# AS3364_quad_VCA_0402_DIL-non_inv_v1_0.net
KiCad netlist of a schematic drawn in EAGLE
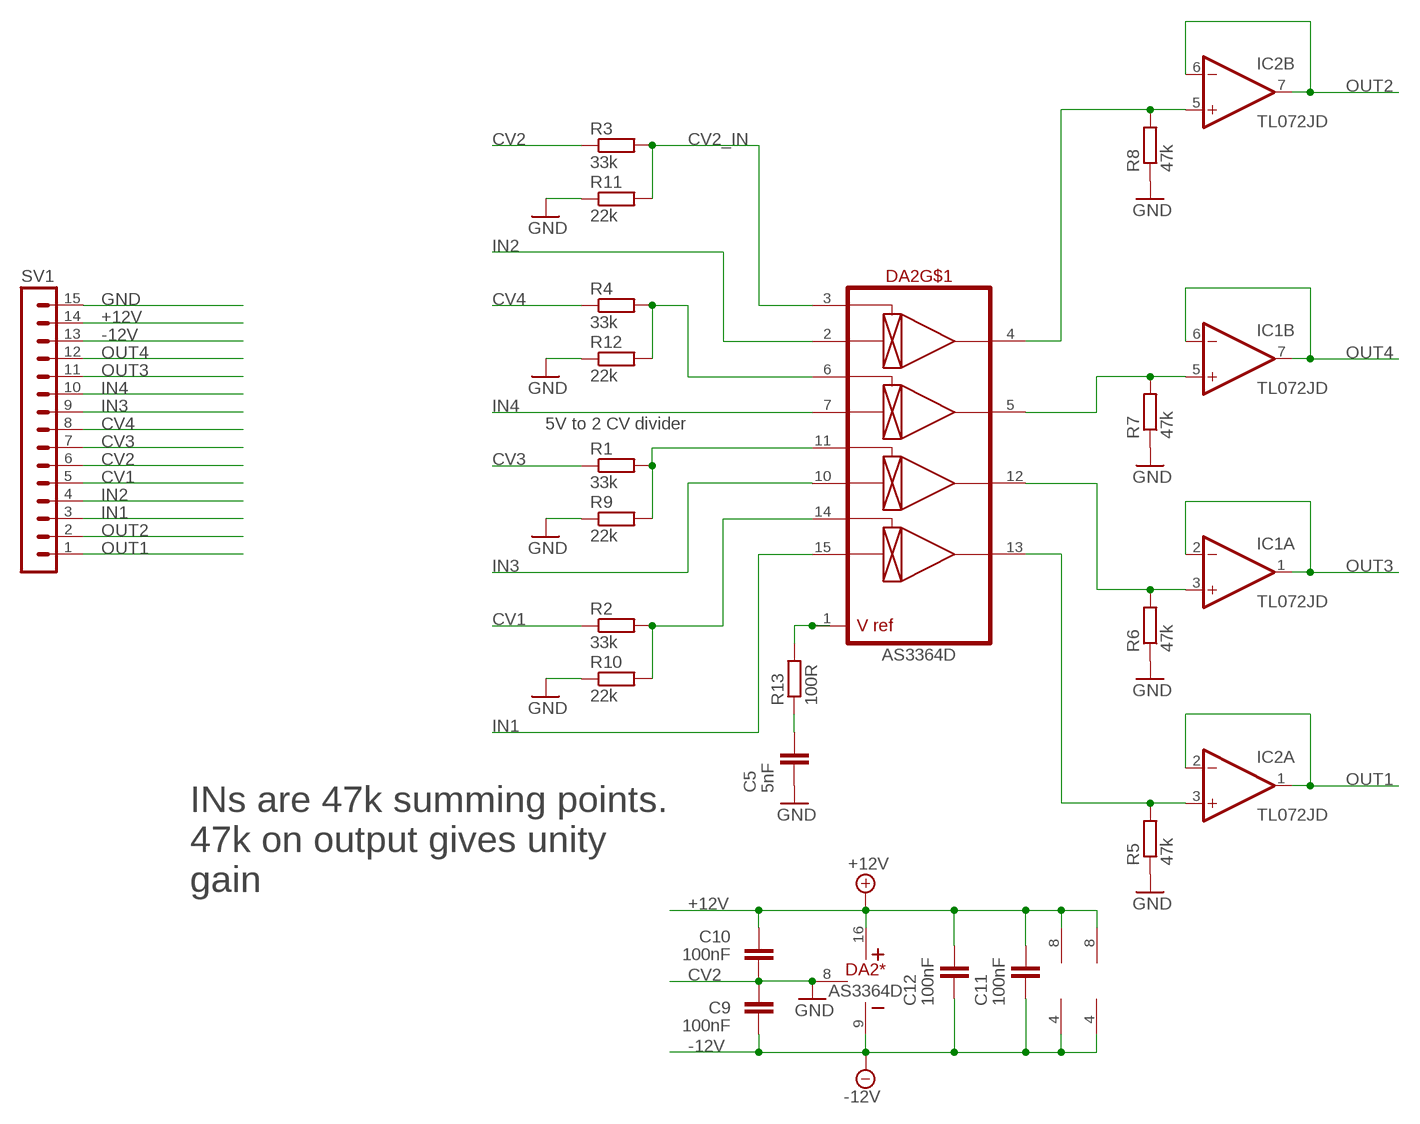
[diagram p0: schematic, sheet 1]

(export (version "E")
  (design (tool "Eeschema 10.0.6"))
  (components
    (comp (ref "C5")
      (value "5nF")
      (footprint "eagle-import:C0402")
      (libsource (lib "eagle-import") (part "C-EUC0402"))
    )
    (comp (ref "C9")
      (value "100nF")
      (footprint "eagle-import:C0402")
      (libsource (lib "eagle-import") (part "C-EUC0402"))
    )
    (comp (ref "C10")
      (value "100nF")
      (footprint "eagle-import:C0402")
      (libsource (lib "eagle-import") (part "C-EUC0402"))
    )
    (comp (ref "C11")
      (value "100nF")
      (footprint "eagle-import:C0402")
      (libsource (lib "eagle-import") (part "C-EUC0402"))
    )
    (comp (ref "C12")
      (value "100nF")
      (footprint "eagle-import:C0402")
      (libsource (lib "eagle-import") (part "C-EUC0402"))
    )
    (comp (ref "DA2")
      (value "AS3364D")
      (footprint "eagle-import:DIL16J")
      (libsource (lib "eagle-import") (part "AS3364D"))
    )
    (comp (ref "IC1")
      (value "TL072JD")
      (footprint "eagle-import:SO08J")
      (libsource (lib "eagle-import") (part "TL072JD"))
    )
    (comp (ref "IC2")
      (value "TL072JD")
      (footprint "eagle-import:SO08J")
      (libsource (lib "eagle-import") (part "TL072JD"))
    )
    (comp (ref "R1")
      (value "33k")
      (footprint "eagle-import:R0402")
      (libsource (lib "eagle-import") (part "R-EU_R0402"))
    )
    (comp (ref "R2")
      (value "33k")
      (footprint "eagle-import:R0402")
      (libsource (lib "eagle-import") (part "R-EU_R0402"))
    )
    (comp (ref "R3")
      (value "33k")
      (footprint "eagle-import:R0402")
      (libsource (lib "eagle-import") (part "R-EU_R0402"))
    )
    (comp (ref "R4")
      (value "33k")
      (footprint "eagle-import:R0402")
      (libsource (lib "eagle-import") (part "R-EU_R0402"))
    )
    (comp (ref "R5")
      (value "47k")
      (footprint "eagle-import:R0402")
      (libsource (lib "eagle-import") (part "R-EU_R0402"))
    )
    (comp (ref "R6")
      (value "47k")
      (footprint "eagle-import:R0402")
      (libsource (lib "eagle-import") (part "R-EU_R0402"))
    )
    (comp (ref "R7")
      (value "47k")
      (footprint "eagle-import:R0402")
      (libsource (lib "eagle-import") (part "R-EU_R0402"))
    )
    (comp (ref "R8")
      (value "47k")
      (footprint "eagle-import:R0402")
      (libsource (lib "eagle-import") (part "R-EU_R0402"))
    )
    (comp (ref "R9")
      (value "22k")
      (footprint "eagle-import:R0402")
      (libsource (lib "eagle-import") (part "R-EU_R0402"))
    )
    (comp (ref "R10")
      (value "22k")
      (footprint "eagle-import:R0402")
      (libsource (lib "eagle-import") (part "R-EU_R0402"))
    )
    (comp (ref "R11")
      (value "22k")
      (footprint "eagle-import:R0402")
      (libsource (lib "eagle-import") (part "R-EU_R0402"))
    )
    (comp (ref "R12")
      (value "22k")
      (footprint "eagle-import:R0402")
      (libsource (lib "eagle-import") (part "R-EU_R0402"))
    )
    (comp (ref "R13")
      (value "100R")
      (footprint "eagle-import:R0402")
      (libsource (lib "eagle-import") (part "R-EU_R0402"))
    )
    (comp (ref "SV1")
      (value "MA15-1JP")
      (footprint "eagle-import:SIP-PIN15-1J")
      (libsource (lib "eagle-import") (part "MA15-1JP"))
    )
  )
  (nets
    (net (code "1") (name "+12V") (class "Default")
      (node (ref "C10") (pin "2") (pinfunction "2_2") (pintype "passive"))
      (node (ref "C11") (pin "2") (pinfunction "2_2") (pintype "passive"))
      (node (ref "C12") (pin "2") (pinfunction "2_2") (pintype "passive"))
      (node (ref "DA2") (pin "16") (pinfunction "V+_16") (pintype "power_in"))
      (node (ref "IC1") (pin "8") (pinfunction "V+_8") (pintype "power_in"))
      (node (ref "IC2") (pin "8") (pinfunction "V+_8") (pintype "power_in"))
      (node (ref "SV1") (pin "14") (pinfunction "14_14") (pintype "passive"))
    )
    (net (code "2") (name "-12V") (class "Default")
      (node (ref "C11") (pin "1") (pinfunction "1_1") (pintype "passive"))
      (node (ref "C12") (pin "1") (pinfunction "1_1") (pintype "passive"))
      (node (ref "C9") (pin "1") (pinfunction "1_1") (pintype "passive"))
      (node (ref "DA2") (pin "9") (pinfunction "V-_9") (pintype "power_in"))
      (node (ref "IC1") (pin "4") (pinfunction "V-_4") (pintype "power_in"))
      (node (ref "IC2") (pin "4") (pinfunction "V-_4") (pintype "power_in"))
      (node (ref "SV1") (pin "13") (pinfunction "13_13") (pintype "passive"))
    )
    (net (code "3") (name "/CV1") (class "Default")
      (node (ref "R2") (pin "1") (pinfunction "1_1") (pintype "passive"))
      (node (ref "SV1") (pin "5") (pinfunction "5_5") (pintype "passive"))
    )
    (net (code "4") (name "/CV2") (class "Default")
      (node (ref "R3") (pin "1") (pinfunction "1_1") (pintype "passive"))
      (node (ref "SV1") (pin "6") (pinfunction "6_6") (pintype "passive"))
    )
    (net (code "5") (name "/CV2_IN") (class "Default")
      (node (ref "DA2") (pin "3") (pinfunction "CV1_3") (pintype "input"))
      (node (ref "R11") (pin "2") (pinfunction "2_2") (pintype "passive"))
      (node (ref "R3") (pin "2") (pinfunction "2_2") (pintype "passive"))
    )
    (net (code "6") (name "/CV3") (class "Default")
      (node (ref "R1") (pin "1") (pinfunction "1_1") (pintype "passive"))
      (node (ref "SV1") (pin "7") (pinfunction "7_7") (pintype "passive"))
    )
    (net (code "7") (name "/CV4") (class "Default")
      (node (ref "R4") (pin "1") (pinfunction "1_1") (pintype "passive"))
      (node (ref "SV1") (pin "8") (pinfunction "8_8") (pintype "passive"))
    )
    (net (code "8") (name "/IN1") (class "Default")
      (node (ref "DA2") (pin "15") (pinfunction "IN4_15") (pintype "input"))
      (node (ref "SV1") (pin "3") (pinfunction "3_3") (pintype "passive"))
    )
    (net (code "9") (name "/IN2") (class "Default")
      (node (ref "DA2") (pin "2") (pinfunction "IN1_2") (pintype "input"))
      (node (ref "SV1") (pin "4") (pinfunction "4_4") (pintype "passive"))
    )
    (net (code "10") (name "/IN3") (class "Default")
      (node (ref "DA2") (pin "10") (pinfunction "IN3_10") (pintype "input"))
      (node (ref "SV1") (pin "9") (pinfunction "9_9") (pintype "passive"))
    )
    (net (code "11") (name "/IN4") (class "Default")
      (node (ref "DA2") (pin "7") (pinfunction "IN2_7") (pintype "input"))
      (node (ref "SV1") (pin "10") (pinfunction "10_10") (pintype "passive"))
    )
    (net (code "12") (name "/OUT1") (class "Default")
      (node (ref "IC2") (pin "1") (pinfunction "OUT_1") (pintype "output"))
      (node (ref "IC2") (pin "2") (pinfunction "-IN_2") (pintype "input"))
      (node (ref "SV1") (pin "1") (pinfunction "1_1") (pintype "passive"))
    )
    (net (code "13") (name "/OUT2") (class "Default")
      (node (ref "IC2") (pin "6") (pinfunction "-IN_6") (pintype "input"))
      (node (ref "IC2") (pin "7") (pinfunction "OUT_7") (pintype "output"))
      (node (ref "SV1") (pin "2") (pinfunction "2_2") (pintype "passive"))
    )
    (net (code "14") (name "/OUT3") (class "Default")
      (node (ref "IC1") (pin "1") (pinfunction "OUT_1") (pintype "output"))
      (node (ref "IC1") (pin "2") (pinfunction "-IN_2") (pintype "input"))
      (node (ref "SV1") (pin "11") (pinfunction "11_11") (pintype "passive"))
    )
    (net (code "15") (name "/OUT4") (class "Default")
      (node (ref "IC1") (pin "6") (pinfunction "-IN_6") (pintype "input"))
      (node (ref "IC1") (pin "7") (pinfunction "OUT_7") (pintype "output"))
      (node (ref "SV1") (pin "12") (pinfunction "12_12") (pintype "passive"))
    )
    (net (code "16") (name "GND") (class "Default")
      (node (ref "C10") (pin "1") (pinfunction "1_1") (pintype "passive"))
      (node (ref "C5") (pin "1") (pinfunction "1_1") (pintype "passive"))
      (node (ref "C9") (pin "2") (pinfunction "2_2") (pintype "passive"))
      (node (ref "DA2") (pin "8") (pinfunction "GND_8") (pintype "power_in"))
      (node (ref "R10") (pin "1") (pinfunction "1_1") (pintype "passive"))
      (node (ref "R11") (pin "1") (pinfunction "1_1") (pintype "passive"))
      (node (ref "R12") (pin "1") (pinfunction "1_1") (pintype "passive"))
      (node (ref "R5") (pin "1") (pinfunction "1_1") (pintype "passive"))
      (node (ref "R6") (pin "1") (pinfunction "1_1") (pintype "passive"))
      (node (ref "R7") (pin "1") (pinfunction "1_1") (pintype "passive"))
      (node (ref "R8") (pin "1") (pinfunction "1_1") (pintype "passive"))
      (node (ref "R9") (pin "1") (pinfunction "1_1") (pintype "passive"))
      (node (ref "SV1") (pin "15") (pinfunction "15_15") (pintype "passive"))
    )
    (net (code "17") (name "Net-(C5-Pad2)") (class "Default")
      (node (ref "C5") (pin "2") (pinfunction "2_2") (pintype "passive"))
      (node (ref "R13") (pin "1") (pinfunction "1_1") (pintype "passive"))
    )
    (net (code "18") (name "Net-(DA2B-CV2)") (class "Default")
      (node (ref "DA2") (pin "6") (pinfunction "CV2_6") (pintype "input"))
      (node (ref "R12") (pin "2") (pinfunction "2_2") (pintype "passive"))
      (node (ref "R4") (pin "2") (pinfunction "2_2") (pintype "passive"))
    )
    (net (code "19") (name "Net-(DA2B-CV3)") (class "Default")
      (node (ref "DA2") (pin "11") (pinfunction "CV3_11") (pintype "input"))
      (node (ref "R1") (pin "2") (pinfunction "2_2") (pintype "passive"))
      (node (ref "R9") (pin "2") (pinfunction "2_2") (pintype "passive"))
    )
    (net (code "20") (name "Net-(DA2B-CV4)") (class "Default")
      (node (ref "DA2") (pin "14") (pinfunction "CV4_14") (pintype "input"))
      (node (ref "R10") (pin "2") (pinfunction "2_2") (pintype "passive"))
      (node (ref "R2") (pin "2") (pinfunction "2_2") (pintype "passive"))
    )
    (net (code "21") (name "Net-(DA2B-OUT1)") (class "Default")
      (node (ref "DA2") (pin "4") (pinfunction "OUT1_4") (pintype "output"))
      (node (ref "IC2") (pin "5") (pinfunction "+IN_5") (pintype "input"))
      (node (ref "R8") (pin "2") (pinfunction "2_2") (pintype "passive"))
    )
    (net (code "22") (name "Net-(DA2B-OUT2)") (class "Default")
      (node (ref "DA2") (pin "5") (pinfunction "OUT2_5") (pintype "output"))
      (node (ref "IC1") (pin "5") (pinfunction "+IN_5") (pintype "input"))
      (node (ref "R7") (pin "2") (pinfunction "2_2") (pintype "passive"))
    )
    (net (code "23") (name "Net-(DA2B-OUT3)") (class "Default")
      (node (ref "DA2") (pin "12") (pinfunction "OUT3_12") (pintype "output"))
      (node (ref "IC1") (pin "3") (pinfunction "+IN_3") (pintype "input"))
      (node (ref "R6") (pin "2") (pinfunction "2_2") (pintype "passive"))
    )
    (net (code "24") (name "Net-(DA2B-OUT4)") (class "Default")
      (node (ref "DA2") (pin "13") (pinfunction "OUT4_13") (pintype "output"))
      (node (ref "IC2") (pin "3") (pinfunction "+IN_3") (pintype "input"))
      (node (ref "R5") (pin "2") (pinfunction "2_2") (pintype "passive"))
    )
    (net (code "25") (name "Net-(DA2B-VREF)") (class "Default")
      (node (ref "DA2") (pin "1") (pinfunction "VREF_1") (pintype "output"))
      (node (ref "R13") (pin "2") (pinfunction "2_2") (pintype "passive"))
    )
  )
)
